# SCH_DINKI-BLINKI_2026-09-26.net
KiCad netlist of a schematic drawn in EasyEDA
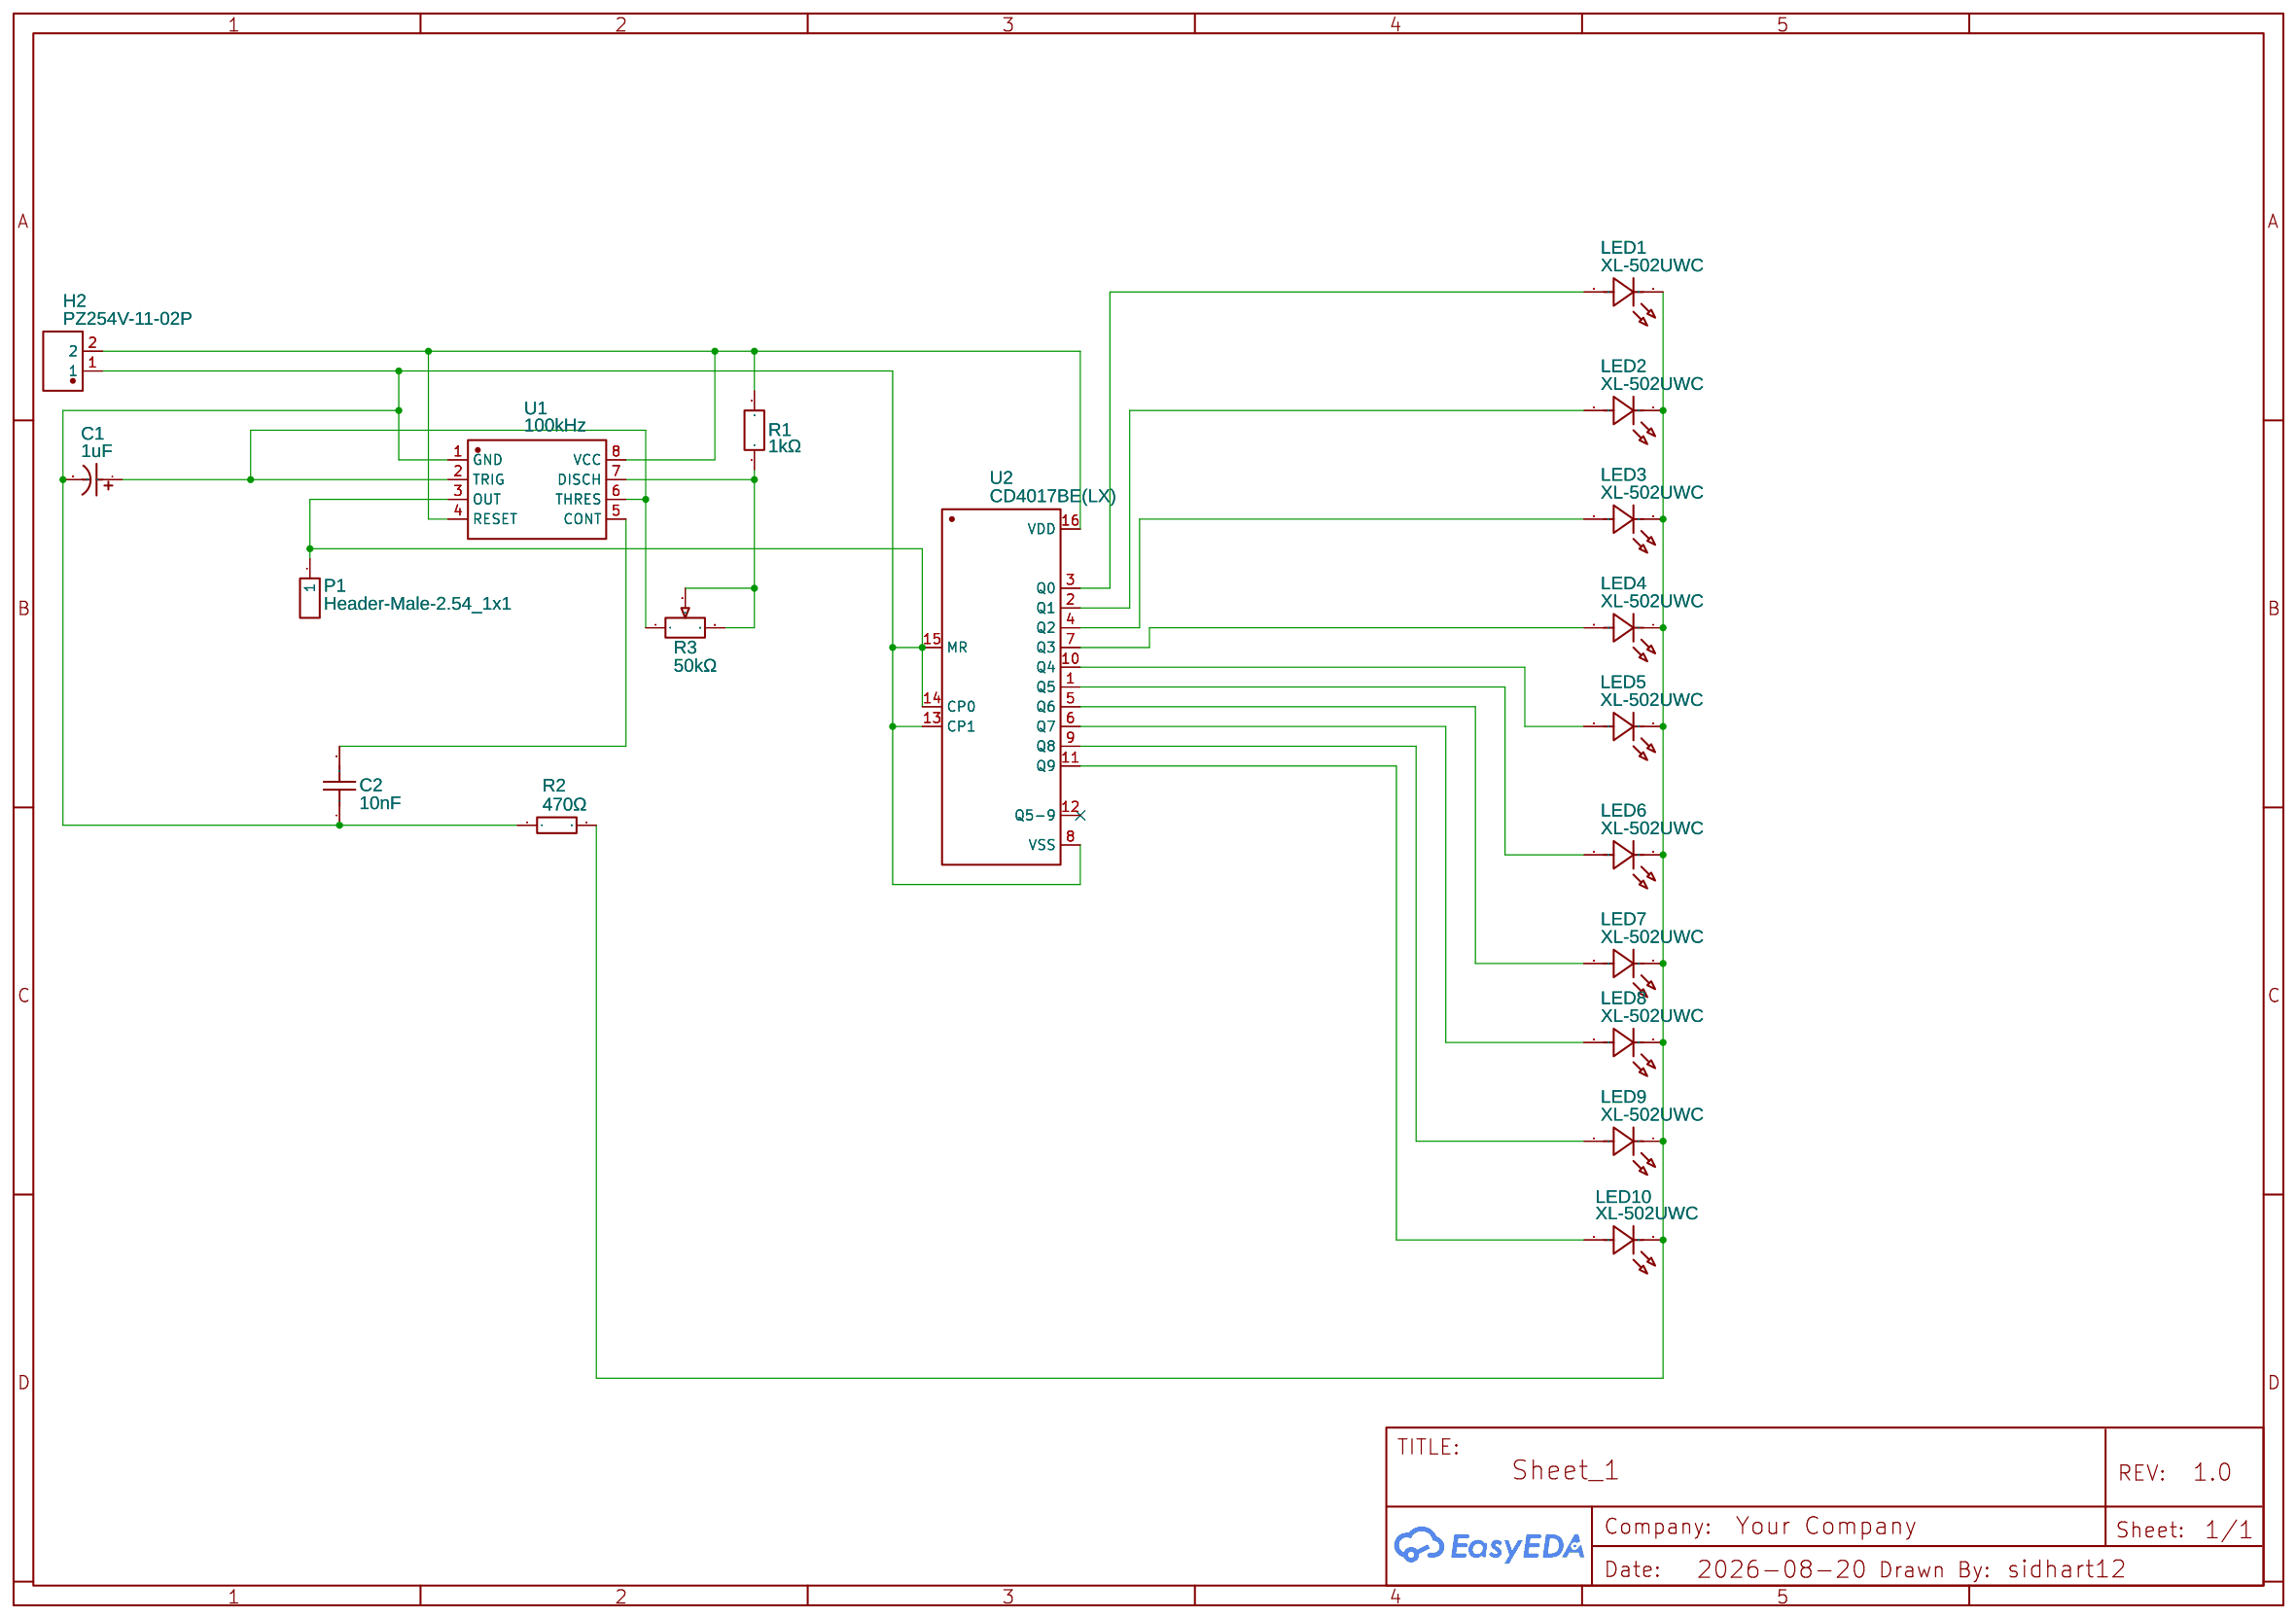
[diagram p0: schematic sheet]

(export (version "E")
  (design (tool "Eeschema 10.0.6"))
  (components
    (comp (ref "C1")
      (value "1uF")
      (fields (field (name "Manufacturer Part") "KF010M050C110A") (field (name "Manufacturer") "CapXon(丰宾)"))
      (libsource (lib "") (part "KF010M050C110A"))
    )
    (comp (ref "C2")
      (value "10nF")
      (fields (field (name "Manufacturer Part") "N09F1B103MN0B0S0N0") (field (name "Manufacturer") "STE(松田)"))
      (libsource (lib "") (part "N09F1B103MN0B0S0N0"))
    )
    (comp (ref "H2")
      (value "PZ254V-11-02P")
      (fields (field (name "Manufacturer") "XFCN(兴飞)"))
      (libsource (lib "") (part "PZ254V-11-02P"))
    )
    (comp (ref "LED1")
      (value "XL-502UWC")
      (fields (field (name "Manufacturer") "XINGLIGHT(成兴光)"))
      (libsource (lib "") (part "XL-502UWC"))
    )
    (comp (ref "LED2")
      (value "XL-502UWC")
      (fields (field (name "Manufacturer") "XINGLIGHT(成兴光)"))
      (libsource (lib "") (part "XL-502UWC"))
    )
    (comp (ref "LED3")
      (value "XL-502UWC")
      (fields (field (name "Manufacturer") "XINGLIGHT(成兴光)"))
      (libsource (lib "") (part "XL-502UWC"))
    )
    (comp (ref "LED4")
      (value "XL-502UWC")
      (fields (field (name "Manufacturer") "XINGLIGHT(成兴光)"))
      (libsource (lib "") (part "XL-502UWC"))
    )
    (comp (ref "LED5")
      (value "XL-502UWC")
      (fields (field (name "Manufacturer") "XINGLIGHT(成兴光)"))
      (libsource (lib "") (part "XL-502UWC"))
    )
    (comp (ref "LED6")
      (value "XL-502UWC")
      (fields (field (name "Manufacturer") "XINGLIGHT(成兴光)"))
      (libsource (lib "") (part "XL-502UWC"))
    )
    (comp (ref "LED7")
      (value "XL-502UWC")
      (fields (field (name "Manufacturer") "XINGLIGHT(成兴光)"))
      (libsource (lib "") (part "XL-502UWC"))
    )
    (comp (ref "LED8")
      (value "XL-502UWC")
      (fields (field (name "Manufacturer") "XINGLIGHT(成兴光)"))
      (libsource (lib "") (part "XL-502UWC"))
    )
    (comp (ref "LED9")
      (value "XL-502UWC")
      (fields (field (name "Manufacturer") "XINGLIGHT(成兴光)"))
      (libsource (lib "") (part "XL-502UWC"))
    )
    (comp (ref "LED10")
      (value "XL-502UWC")
      (fields (field (name "Manufacturer") "XINGLIGHT(成兴光)"))
      (libsource (lib "") (part "XL-502UWC"))
    )
    (comp (ref "P1")
      (value "Header-Male-2.54_1x1")
      (fields (field (name "Manufacturer Part") "2.54-1*1P针") (field (name "Manufacturer") "BOOMELE(博穆精密)"))
      (libsource (lib "") (part "Header-Male-2.54_1x1"))
    )
    (comp (ref "R1")
      (value "1kΩ")
      (fields (field (name "Manufacturer Part") "MF1/4W-1KΩ±1%T52") (field (name "Manufacturer") "华星机电"))
      (libsource (lib "") (part "MF1/4W-1KΩ±1%T52"))
    )
    (comp (ref "R2")
      (value "470Ω")
      (fields
        (field (name "Manufacturer Part") "MFR0W4F4700A50")
        (field (name "Manufacturer") "UNI-ROYAL(厚声)")
      )
      (libsource (lib "") (part "MFR0W4F4700A50"))
    )
    (comp (ref "R3")
      (value "50kΩ")
      (fields (field (name "Manufacturer Part") "3296X-1-503") (field (name "Manufacturer") "BOCHEN(博晨)"))
      (libsource (lib "") (part "3296X-1-503_C118912"))
    )
    (comp (ref "U1")
      (value "100kHz")
      (fields (field (name "Manufacturer Part") "NE555P") (field (name "Manufacturer") "TI(德州仪器)"))
      (libsource (lib "") (part "NE555P"))
    )
    (comp (ref "U2")
      (value "CD4017BE(LX)")
      (fields (field (name "Manufacturer") "LX(灵星芯微)"))
      (libsource (lib "") (part "CD4017BE(LX)"))
    )
  )
  (nets
    (net (code "1") (name "Net-(LED1-A)") (class "Default")
      (node (ref "LED1") (pin "2") (pinfunction "A_2") (pintype "unspecified"))
      (node (ref "U2") (pin "3") (pinfunction "Q0_3") (pintype "unspecified"))
    )
    (net (code "2") (name "Net-(LED1-K)") (class "Default")
      (node (ref "LED1") (pin "1") (pinfunction "K_1") (pintype "unspecified"))
      (node (ref "LED10") (pin "1") (pinfunction "K_1") (pintype "unspecified"))
      (node (ref "LED2") (pin "1") (pinfunction "K_1") (pintype "unspecified"))
      (node (ref "LED3") (pin "1") (pinfunction "K_1") (pintype "unspecified"))
      (node (ref "LED4") (pin "1") (pinfunction "K_1") (pintype "unspecified"))
      (node (ref "LED5") (pin "1") (pinfunction "K_1") (pintype "unspecified"))
      (node (ref "LED6") (pin "1") (pinfunction "K_1") (pintype "unspecified"))
      (node (ref "LED7") (pin "1") (pinfunction "K_1") (pintype "unspecified"))
      (node (ref "LED8") (pin "1") (pinfunction "K_1") (pintype "unspecified"))
      (node (ref "LED9") (pin "1") (pinfunction "K_1") (pintype "unspecified"))
      (node (ref "R2") (pin "2") (pinfunction "2_2") (pintype "input"))
    )
    (net (code "3") (name "Net-(LED2-A)") (class "Default")
      (node (ref "LED2") (pin "2") (pinfunction "A_2") (pintype "unspecified"))
      (node (ref "U2") (pin "2") (pinfunction "Q1_2") (pintype "unspecified"))
    )
    (net (code "4") (name "Net-(LED3-A)") (class "Default")
      (node (ref "LED3") (pin "2") (pinfunction "A_2") (pintype "unspecified"))
      (node (ref "U2") (pin "4") (pinfunction "Q2_4") (pintype "unspecified"))
    )
    (net (code "5") (name "Net-(LED4-A)") (class "Default")
      (node (ref "LED4") (pin "2") (pinfunction "A_2") (pintype "unspecified"))
      (node (ref "U2") (pin "7") (pinfunction "Q3_7") (pintype "unspecified"))
    )
    (net (code "6") (name "Net-(LED5-A)") (class "Default")
      (node (ref "LED5") (pin "2") (pinfunction "A_2") (pintype "unspecified"))
      (node (ref "U2") (pin "10") (pinfunction "Q4_10") (pintype "unspecified"))
    )
    (net (code "7") (name "Net-(LED6-A)") (class "Default")
      (node (ref "LED6") (pin "2") (pinfunction "A_2") (pintype "unspecified"))
      (node (ref "U2") (pin "1") (pinfunction "Q5_1") (pintype "unspecified"))
    )
    (net (code "8") (name "Net-(LED7-A)") (class "Default")
      (node (ref "LED7") (pin "2") (pinfunction "A_2") (pintype "unspecified"))
      (node (ref "U2") (pin "5") (pinfunction "Q6_5") (pintype "unspecified"))
    )
    (net (code "9") (name "Net-(LED8-A)") (class "Default")
      (node (ref "LED8") (pin "2") (pinfunction "A_2") (pintype "unspecified"))
      (node (ref "U2") (pin "6") (pinfunction "Q7_6") (pintype "unspecified"))
    )
    (net (code "10") (name "Net-(LED9-A)") (class "Default")
      (node (ref "LED9") (pin "2") (pinfunction "A_2") (pintype "unspecified"))
      (node (ref "U2") (pin "9") (pinfunction "Q8_9") (pintype "unspecified"))
    )
    (net (code "11") (name "Net-(LED10-A)") (class "Default")
      (node (ref "LED10") (pin "2") (pinfunction "A_2") (pintype "unspecified"))
      (node (ref "U2") (pin "11") (pinfunction "Q9_11") (pintype "unspecified"))
    )
    (net (code "12") (name "Net-(U1-CONT)") (class "Default")
      (node (ref "C2") (pin "2") (pinfunction "2_2") (pintype "unspecified"))
      (node (ref "U1") (pin "5") (pinfunction "CONT_5") (pintype "unspecified"))
    )
    (net (code "13") (name "Net-(U1-DISCH)") (class "Default")
      (node (ref "R1") (pin "1") (pinfunction "1_1") (pintype "unspecified"))
      (node (ref "R3") (pin "2") (pinfunction "2_2") (pintype "input"))
      (node (ref "R3") (pin "3") (pinfunction "3_3") (pintype "input"))
      (node (ref "U1") (pin "7") (pinfunction "DISCH_7") (pintype "unspecified"))
    )
    (net (code "14") (name "Net-(U1-GND)") (class "Default")
      (node (ref "C1") (pin "2") (pinfunction "2_2") (pintype "input"))
      (node (ref "C2") (pin "1") (pinfunction "1_1") (pintype "unspecified"))
      (node (ref "H2") (pin "1") (pinfunction "1_1") (pintype "unspecified"))
      (node (ref "P1") (pin "1") (pinfunction "1_1") (pintype "input"))
      (node (ref "R2") (pin "1") (pinfunction "1_1") (pintype "input"))
      (node (ref "U1") (pin "1") (pinfunction "GND_1") (pintype "unspecified"))
      (node (ref "U1") (pin "3") (pinfunction "OUT_3") (pintype "unspecified"))
      (node (ref "U2") (pin "13") (pinfunction "CP1_13") (pintype "unspecified"))
      (node (ref "U2") (pin "14") (pinfunction "CP0_14") (pintype "unspecified"))
      (node (ref "U2") (pin "15") (pinfunction "MR_15") (pintype "unspecified"))
      (node (ref "U2") (pin "8") (pinfunction "VSS_8") (pintype "unspecified"))
    )
    (net (code "15") (name "Net-(U1-RESET)") (class "Default")
      (node (ref "H2") (pin "2") (pinfunction "2_2") (pintype "unspecified"))
      (node (ref "R1") (pin "2") (pinfunction "2_2") (pintype "unspecified"))
      (node (ref "U1") (pin "4") (pinfunction "RESET_4") (pintype "unspecified"))
      (node (ref "U1") (pin "8") (pinfunction "VCC_8") (pintype "unspecified"))
      (node (ref "U2") (pin "16") (pinfunction "VDD_16") (pintype "unspecified"))
    )
    (net (code "16") (name "Net-(U1-THRES)") (class "Default")
      (node (ref "C1") (pin "1") (pinfunction "1_1") (pintype "input"))
      (node (ref "R3") (pin "1") (pinfunction "1_1") (pintype "input"))
      (node (ref "U1") (pin "2") (pinfunction "TRIG_2") (pintype "unspecified"))
      (node (ref "U1") (pin "6") (pinfunction "THRES_6") (pintype "unspecified"))
    )
    (net (code "17") (name "unconnected-(U2-Q5-9-Pad12)") (class "Default")
      (node (ref "U2") (pin "12") (pinfunction "Q5-9_12") (pintype "unspecified+no_connect"))
    )
  )
)
